# lcd_duffle_pth_mk_5.net
KiCad netlist of a schematic drawn in EAGLE
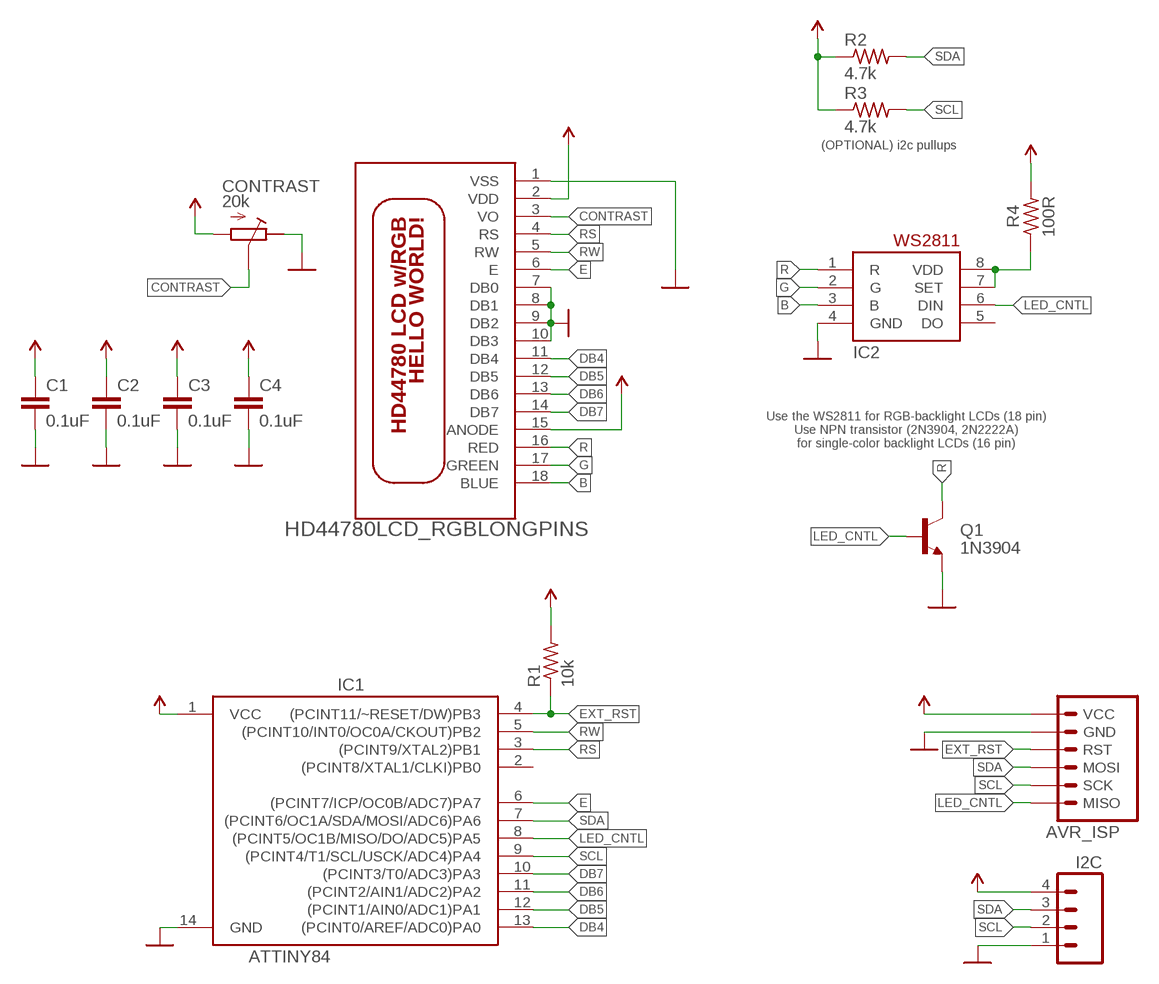
[diagram p0: schematic, sheet 1]

(export (version "E")
  (design (tool "Eeschema 10.0.6"))
  (components
    (comp (ref "AVR_ISP")
      (value "AVR_MINI_PROGJST-XH-RA-PTH")
      (footprint "eagle-import:AVR_MINI_PROG_JST_XH_RA")
      (libsource (lib "eagle-import") (part "AVR_MINI_PROGJST-XH-RA-PTH"))
    )
    (comp (ref "C1")
      (value "0.1uF")
      (footprint "eagle-import:C025-024X044")
      (libsource (lib "eagle-import") (part "CAPACITOR-CERAMIC025-024X044"))
    )
    (comp (ref "C2")
      (value "0.1uF")
      (footprint "eagle-import:C025-024X044")
      (libsource (lib "eagle-import") (part "CAPACITOR-CERAMIC025-024X044"))
    )
    (comp (ref "C3")
      (value "0.1uF")
      (footprint "eagle-import:C025-024X044")
      (libsource (lib "eagle-import") (part "CAPACITOR-CERAMIC025-024X044"))
    )
    (comp (ref "C4")
      (value "0.1uF")
      (footprint "eagle-import:C025-024X044")
      (libsource (lib "eagle-import") (part "CAPACITOR-CERAMIC025-024X044"))
    )
    (comp (ref "CONTRAST")
      (value "20k")
      (footprint "eagle-import:POT-THUMBWHEEL")
      (libsource (lib "eagle-import") (part "POTENTIOMETERTHUMBWHEEL-16MM"))
    )
    (comp (ref "I2C")
      (value "M04JST_XH_RA")
      (footprint "eagle-import:JST-4-XH-RA-PTH")
      (libsource (lib "eagle-import") (part "M04JST_XH_RA"))
    )
    (comp (ref "IC1")
      (value "ATTINY84")
      (footprint "eagle-import:DIL14")
      (libsource (lib "eagle-import") (part "ATTINY84ATTINY84-20PU"))
    )
    (comp (ref "IC2")
      (value "WS2811")
      (footprint "eagle-import:SO08-SKINNYPADS")
      (libsource (lib "eagle-import") (part "WS2811-SOP8"))
    )
    (comp (ref "Q1")
      (value "1N3904")
      (footprint "eagle-import:TO-92-AMMO")
      (libsource (lib "eagle-import") (part "TRANSISTOR_NPNTO-92-AMMO"))
    )
    (comp (ref "R1")
      (value "10k")
      (footprint "eagle-import:RESISTOR-AXIAL-PTH-5.08MM")
      (libsource (lib "eagle-import") (part "RESISTORPTH-AXIAL-5.08MM"))
    )
    (comp (ref "R2")
      (value "4.7k")
      (footprint "eagle-import:RESISTOR-AXIAL-PTH-5.08MM")
      (libsource (lib "eagle-import") (part "RESISTORPTH-AXIAL-5.08MM"))
    )
    (comp (ref "R3")
      (value "4.7k")
      (footprint "eagle-import:RESISTOR-AXIAL-PTH-5.08MM")
      (libsource (lib "eagle-import") (part "RESISTORPTH-AXIAL-5.08MM"))
    )
    (comp (ref "R4")
      (value "100R")
      (footprint "eagle-import:RESISTOR-AXIAL-PTH-5.08MM")
      (libsource (lib "eagle-import") (part "RESISTORPTH-AXIAL-5.08MM"))
    )
    (comp (ref "U$1")
      (value "HD44780LCD_RGBLONGPINS")
      (footprint "eagle-import:LCD1602-RGB-CENTERED")
      (libsource (lib "eagle-import") (part "HD44780LCD_RGBLONGPINS"))
    )
  )
  (nets
    (net (code "1") (name "5V") (class "Default")
      (node (ref "AVR_ISP") (pin "2") (pinfunction "VCC_2") (pintype "passive"))
      (node (ref "C1") (pin "2") (pinfunction "2_2") (pintype "passive"))
      (node (ref "C2") (pin "2") (pinfunction "2_2") (pintype "passive"))
      (node (ref "C3") (pin "2") (pinfunction "2_2") (pintype "passive"))
      (node (ref "C4") (pin "2") (pinfunction "2_2") (pintype "passive"))
      (node (ref "CONTRAST") (pin "1") (pinfunction "A_1") (pintype "passive"))
      (node (ref "I2C") (pin "4") (pinfunction "4_4") (pintype "passive"))
      (node (ref "IC1") (pin "1") (pinfunction "VCC_1") (pintype "bidirectional"))
      (node (ref "R1") (pin "P$2") (pinfunction "2_P$2") (pintype "passive"))
      (node (ref "R2") (pin "P$1") (pinfunction "1_P$1") (pintype "passive"))
      (node (ref "R3") (pin "P$1") (pinfunction "1_P$1") (pintype "passive"))
      (node (ref "R4") (pin "P$2") (pinfunction "2_P$2") (pintype "passive"))
      (node (ref "U$1") (pin "15") (pinfunction "ANODE_15") (pintype "input"))
      (node (ref "U$1") (pin "2") (pinfunction "VDD_2") (pintype "power_in"))
    )
    (net (code "2") (name "B") (class "Default")
      (node (ref "IC2") (pin "3") (pinfunction "B_3") (pintype "open_collector"))
      (node (ref "U$1") (pin "18") (pinfunction "BLUE_18") (pintype "input"))
    )
    (net (code "3") (name "CONTRAST") (class "Default")
      (node (ref "CONTRAST") (pin "2") (pinfunction "S_2") (pintype "passive"))
      (node (ref "CONTRAST") (pin "2@1") (pinfunction "S_2@1") (pintype "passive"))
      (node (ref "U$1") (pin "3") (pinfunction "VO_3") (pintype "input"))
    )
    (net (code "4") (name "DB4") (class "Default")
      (node (ref "IC1") (pin "13") (pinfunction "(PCINT0/AREF/ADC0)PA0_13") (pintype "bidirectional"))
      (node (ref "U$1") (pin "11") (pinfunction "DB4_11") (pintype "bidirectional"))
    )
    (net (code "5") (name "DB5") (class "Default")
      (node (ref "IC1") (pin "12") (pinfunction "(PCINT1/AIN0/ADC1)PA1_12") (pintype "bidirectional"))
      (node (ref "U$1") (pin "12") (pinfunction "DB5_12") (pintype "bidirectional"))
    )
    (net (code "6") (name "DB6") (class "Default")
      (node (ref "IC1") (pin "11") (pinfunction "(PCINT2/AIN1/ADC2)PA2_11") (pintype "bidirectional"))
      (node (ref "U$1") (pin "13") (pinfunction "DB6_13") (pintype "bidirectional"))
    )
    (net (code "7") (name "DB7") (class "Default")
      (node (ref "IC1") (pin "10") (pinfunction "(PCINT3/T0/ADC3)PA3_10") (pintype "bidirectional"))
      (node (ref "U$1") (pin "14") (pinfunction "DB7_14") (pintype "bidirectional"))
    )
    (net (code "8") (name "E") (class "Default")
      (node (ref "IC1") (pin "6") (pinfunction "(PCINT7/ICP/OC0B/ADC7)PA7_6") (pintype "bidirectional"))
      (node (ref "U$1") (pin "6") (pinfunction "E_6") (pintype "input"))
    )
    (net (code "9") (name "EXT_RST") (class "Default")
      (node (ref "AVR_ISP") (pin "5") (pinfunction "RST_5") (pintype "passive"))
      (node (ref "IC1") (pin "4") (pinfunction "(PCINT11/~{RESET/DW})PB3_4") (pintype "bidirectional"))
      (node (ref "R1") (pin "P$1") (pinfunction "1_P$1") (pintype "passive"))
    )
    (net (code "10") (name "G") (class "Default")
      (node (ref "IC2") (pin "2") (pinfunction "G_2") (pintype "open_collector"))
      (node (ref "U$1") (pin "17") (pinfunction "GREEN_17") (pintype "input"))
    )
    (net (code "11") (name "GND") (class "Default")
      (node (ref "AVR_ISP") (pin "6") (pinfunction "GND_6") (pintype "passive"))
      (node (ref "C1") (pin "1") (pinfunction "1_1") (pintype "passive"))
      (node (ref "C2") (pin "1") (pinfunction "1_1") (pintype "passive"))
      (node (ref "C3") (pin "1") (pinfunction "1_1") (pintype "passive"))
      (node (ref "C4") (pin "1") (pinfunction "1_1") (pintype "passive"))
      (node (ref "CONTRAST") (pin "3") (pinfunction "E_3") (pintype "passive"))
      (node (ref "I2C") (pin "1") (pinfunction "1_1") (pintype "passive"))
      (node (ref "IC1") (pin "14") (pinfunction "GND_14") (pintype "bidirectional"))
      (node (ref "IC2") (pin "4") (pinfunction "GND_4") (pintype "power_in"))
      (node (ref "Q1") (pin "1") (pinfunction "E_1") (pintype "passive"))
      (node (ref "U$1") (pin "1") (pinfunction "VSS_1") (pintype "power_in"))
      (node (ref "U$1") (pin "10") (pinfunction "DB3_10") (pintype "bidirectional"))
      (node (ref "U$1") (pin "7") (pinfunction "DB0_7") (pintype "bidirectional"))
      (node (ref "U$1") (pin "8") (pinfunction "DB1_8") (pintype "bidirectional"))
      (node (ref "U$1") (pin "9") (pinfunction "DB2_9") (pintype "bidirectional"))
    )
    (net (code "12") (name "LED_CNTL") (class "Default")
      (node (ref "AVR_ISP") (pin "1") (pinfunction "MISO_1") (pintype "passive"))
      (node (ref "IC1") (pin "8") (pinfunction "(PCINT5/OC1B/MISO/DO/ADC5)PA5_8") (pintype "bidirectional"))
      (node (ref "IC2") (pin "6") (pinfunction "DIN_6") (pintype "input"))
      (node (ref "Q1") (pin "2") (pinfunction "B_2") (pintype "passive"))
    )
    (net (code "13") (name "Net-(IC2-SET)") (class "Default")
      (node (ref "IC2") (pin "7") (pinfunction "SET_7") (pintype "input"))
      (node (ref "IC2") (pin "8") (pinfunction "VDD_8") (pintype "power_in"))
      (node (ref "R4") (pin "P$1") (pinfunction "1_P$1") (pintype "passive"))
    )
    (net (code "14") (name "R") (class "Default")
      (node (ref "IC2") (pin "1") (pinfunction "R_1") (pintype "open_collector"))
      (node (ref "Q1") (pin "3") (pinfunction "C_3") (pintype "passive"))
      (node (ref "U$1") (pin "16") (pinfunction "RED_16") (pintype "input"))
    )
    (net (code "15") (name "RS") (class "Default")
      (node (ref "IC1") (pin "3") (pinfunction "(PCINT9/XTAL2)PB1_3") (pintype "bidirectional"))
      (node (ref "U$1") (pin "4") (pinfunction "RS_4") (pintype "input"))
    )
    (net (code "16") (name "RW") (class "Default")
      (node (ref "IC1") (pin "5") (pinfunction "(PCINT10/INT0/OC0A/CKOUT)PB2_5") (pintype "bidirectional"))
      (node (ref "U$1") (pin "5") (pinfunction "RW_5") (pintype "input"))
    )
    (net (code "17") (name "SCL") (class "Default")
      (node (ref "AVR_ISP") (pin "3") (pinfunction "SCK_3") (pintype "passive"))
      (node (ref "I2C") (pin "2") (pinfunction "2_2") (pintype "passive"))
      (node (ref "IC1") (pin "9") (pinfunction "(PCINT4/T1/SCL/USCK/ADC4)PA4_9") (pintype "bidirectional"))
      (node (ref "R3") (pin "P$2") (pinfunction "2_P$2") (pintype "passive"))
    )
    (net (code "18") (name "SDA") (class "Default")
      (node (ref "AVR_ISP") (pin "4") (pinfunction "MOSI_4") (pintype "passive"))
      (node (ref "I2C") (pin "3") (pinfunction "3_3") (pintype "passive"))
      (node (ref "IC1") (pin "7") (pinfunction "(PCINT6/OC1A/SDA/MOSI/ADC6)PA6_7") (pintype "bidirectional"))
      (node (ref "R2") (pin "P$2") (pinfunction "2_P$2") (pintype "passive"))
    )
    (net (code "19") (name "unconnected-(IC1-(PCINT8{slash}XTAL1{slash}CLKI)PB0-Pad2)") (class "Default")
      (node (ref "IC1") (pin "2") (pinfunction "(PCINT8/XTAL1/CLKI)PB0_2") (pintype "bidirectional"))
    )
    (net (code "20") (name "unconnected-(IC2-DO-Pad5)") (class "Default")
      (node (ref "IC2") (pin "5") (pinfunction "DO_5") (pintype "output"))
    )
  )
)
